# SCH_GPS_lora_mpu_uv_bmp__2022-12-29.net
KiCad netlist of a schematic drawn in EasyEDA
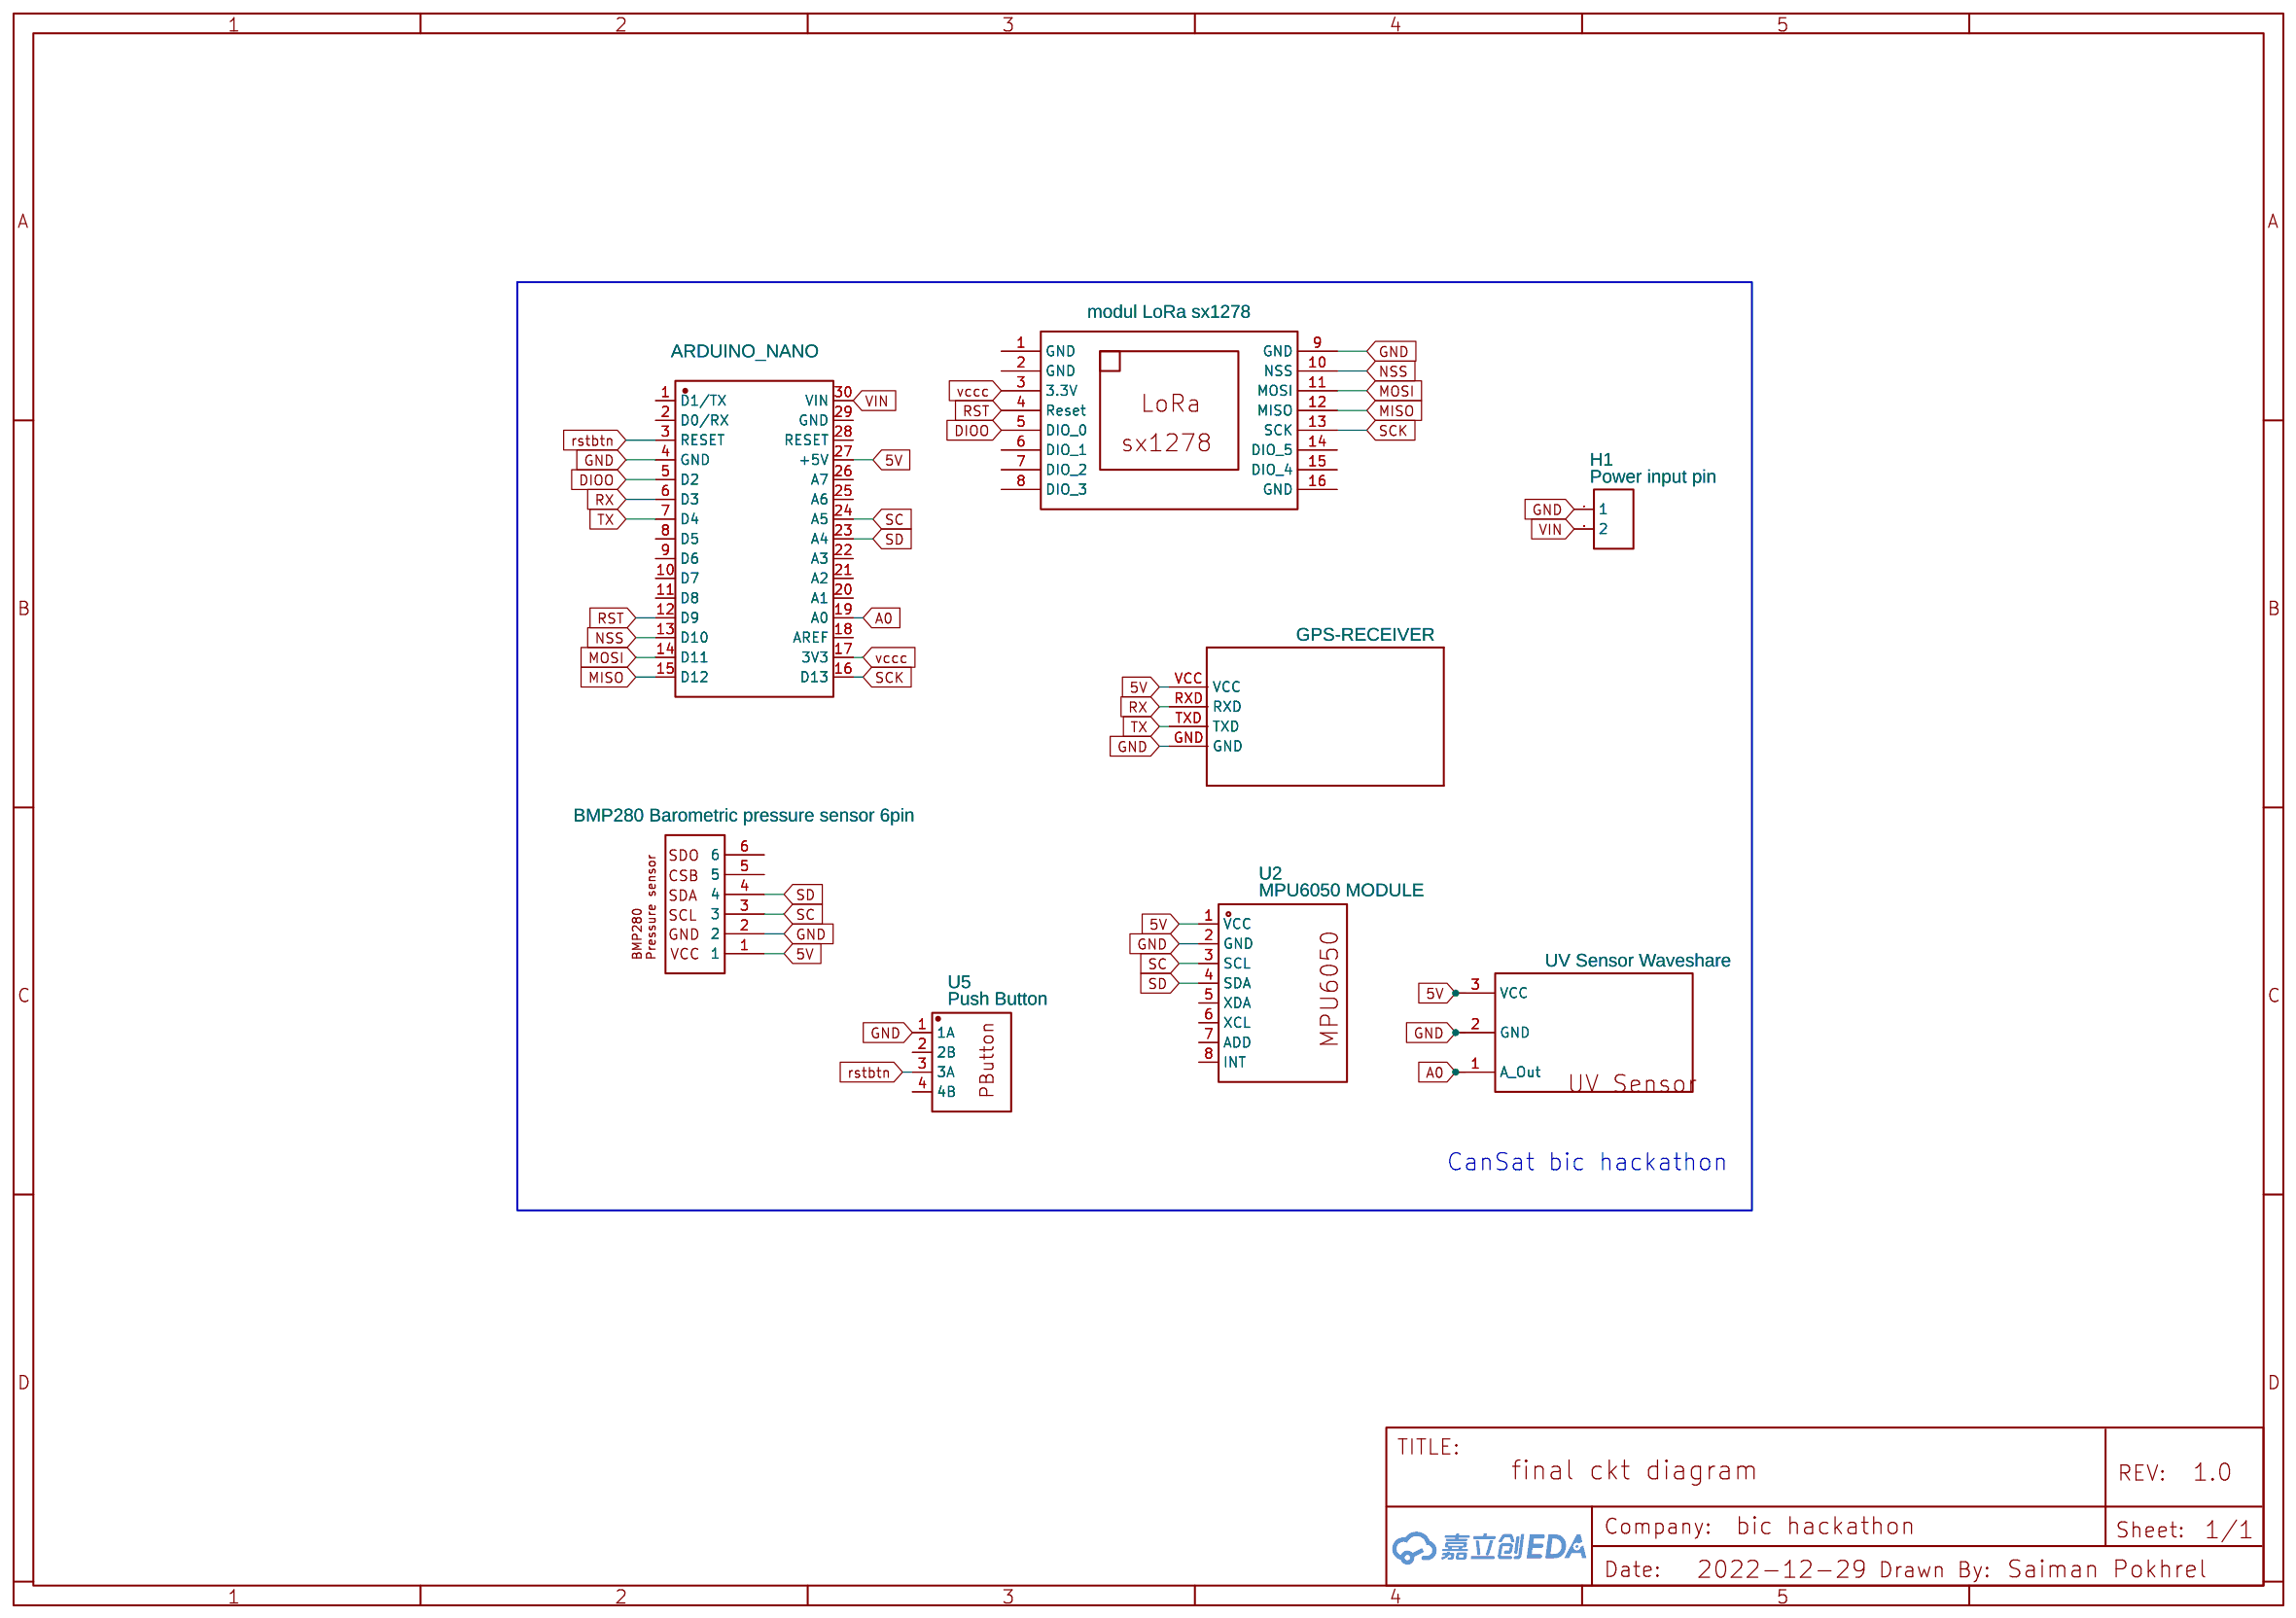
[diagram p0: schematic sheet]

(export (version "E")
  (design (tool "Eeschema 10.0.6"))
  (components
    (comp (ref "1") (value "GPS-RECEIVER") (libsource (lib "") (part "GPS-RECEIVER-NEO8M")))
    (comp (ref "AOUT1")
      (value "UV Sensor Waveshare")
      (fields
        (field (name "BOM_Manufacturer Part") "SKU: 9537")
        (field (name "BOM_Supplier Part") "UV Sensor")
      )
      (libsource (lib "") (part "UV Sensor Waveshare"))
    )
    (comp (ref "H1")
      (value "Power input pin")
      (fields (field (name "BOM_Supplier Part") "C49661"))
      (libsource (lib "") (part "HDR-F-2.54_1x2"))
    )
    (comp (ref "U1")
      (value "BMP280 Barometric pressure sensor 6pin")
      (fields (field (name "BOM_Manufacturer Part") "MAX6675"))
      (libsource (lib "") (part "BMP280 Barometric pressure sensor 6pin"))
    )
    (comp (ref "U2")
      (value "MPU6050 MODULE")
      (fields (field (name "BOM_Manufacturer Part") "MPU6050"))
      (libsource (lib "") (part "MPU6050 MODULE"))
    )
    (comp (ref "U3") (value "modul LoRa sx1278") (libsource (lib "") (part "modul LoRa sx1278")))
    (comp (ref "U4")
      (value "ARDUINO_NANO")
      (fields (field (name "BOM_Supplier Part") "C9900017879"))
      (libsource (lib "") (part "ARDUINO_NANO"))
    )
    (comp (ref "U5") (value "Push Button") (libsource (lib "") (part "Push Button")))
  )
  (nets
    (net (code "1") (name "5V") (class "Default")
      (node (ref "1") (pin "VCC") (pinfunction "VCC_VCC") (pintype "bidirectional"))
      (node (ref "AOUT1") (pin "3") (pinfunction "VCC_3") (pintype "unspecified"))
      (node (ref "U1") (pin "1") (pinfunction "1_1") (pintype "unspecified"))
      (node (ref "U2") (pin "1") (pinfunction "VCC_1") (pintype "passive"))
      (node (ref "U4") (pin "27") (pinfunction "+5V_27") (pintype "unspecified"))
    )
    (net (code "2") (name "A0") (class "Default")
      (node (ref "AOUT1") (pin "1") (pinfunction "A_Out_1") (pintype "unspecified"))
      (node (ref "U4") (pin "19") (pinfunction "A0_19") (pintype "unspecified"))
    )
    (net (code "3") (name "DIOO") (class "Default")
      (node (ref "U3") (pin "5") (pinfunction "DIO_0_5") (pintype "bidirectional"))
      (node (ref "U4") (pin "5") (pinfunction "D2_5") (pintype "unspecified"))
    )
    (net (code "4") (name "GND") (class "Default")
      (node (ref "1") (pin "GND") (pinfunction "GND_GND") (pintype "bidirectional"))
      (node (ref "AOUT1") (pin "2") (pinfunction "GND_2") (pintype "unspecified"))
      (node (ref "H1") (pin "1") (pinfunction "1_1") (pintype "input"))
      (node (ref "U1") (pin "2") (pinfunction "2_2") (pintype "unspecified"))
      (node (ref "U2") (pin "2") (pinfunction "GND_2") (pintype "passive"))
      (node (ref "U3") (pin "9") (pinfunction "GND_9") (pintype "unspecified"))
      (node (ref "U4") (pin "4") (pinfunction "GND_4") (pintype "unspecified"))
      (node (ref "U5") (pin "1") (pinfunction "1A_1") (pintype "unspecified"))
    )
    (net (code "5") (name "MISO") (class "Default")
      (node (ref "U3") (pin "12") (pinfunction "MISO_12") (pintype "output"))
      (node (ref "U4") (pin "15") (pinfunction "D12_15") (pintype "unspecified"))
    )
    (net (code "6") (name "MOSI") (class "Default")
      (node (ref "U3") (pin "11") (pinfunction "MOSI_11") (pintype "input"))
      (node (ref "U4") (pin "14") (pinfunction "D11_14") (pintype "unspecified"))
    )
    (net (code "7") (name "NSS") (class "Default")
      (node (ref "U3") (pin "10") (pinfunction "NSS_10") (pintype "unspecified"))
      (node (ref "U4") (pin "13") (pinfunction "D10_13") (pintype "unspecified"))
    )
    (net (code "8") (name "RST") (class "Default")
      (node (ref "U3") (pin "4") (pinfunction "Reset_4") (pintype "unspecified"))
      (node (ref "U4") (pin "12") (pinfunction "D9_12") (pintype "unspecified"))
    )
    (net (code "9") (name "RX") (class "Default")
      (node (ref "1") (pin "RXD") (pinfunction "RXD_RXD") (pintype "bidirectional"))
      (node (ref "U4") (pin "6") (pinfunction "D3_6") (pintype "unspecified"))
    )
    (net (code "10") (name "SC") (class "Default")
      (node (ref "U1") (pin "3") (pinfunction "3_3") (pintype "unspecified"))
      (node (ref "U2") (pin "3") (pinfunction "SCL_3") (pintype "input"))
      (node (ref "U4") (pin "24") (pinfunction "A5_24") (pintype "unspecified"))
    )
    (net (code "11") (name "SCK") (class "Default")
      (node (ref "U3") (pin "13") (pinfunction "SCK_13") (pintype "unspecified"))
      (node (ref "U4") (pin "16") (pinfunction "D13_16") (pintype "unspecified"))
    )
    (net (code "12") (name "SD") (class "Default")
      (node (ref "U1") (pin "4") (pinfunction "4_4") (pintype "unspecified"))
      (node (ref "U2") (pin "4") (pinfunction "SDA_4") (pintype "bidirectional"))
      (node (ref "U4") (pin "23") (pinfunction "A4_23") (pintype "unspecified"))
    )
    (net (code "13") (name "TX") (class "Default")
      (node (ref "1") (pin "TXD") (pinfunction "TXD_TXD") (pintype "bidirectional"))
      (node (ref "U4") (pin "7") (pinfunction "D4_7") (pintype "unspecified"))
    )
    (net (code "14") (name "VIN") (class "Default")
      (node (ref "H1") (pin "2") (pinfunction "2_2") (pintype "input"))
      (node (ref "U4") (pin "30") (pinfunction "VIN_30") (pintype "unspecified"))
    )
    (net (code "15") (name "rstbtn") (class "Default")
      (node (ref "U4") (pin "3") (pinfunction "RESET_3") (pintype "unspecified"))
      (node (ref "U5") (pin "3") (pinfunction "3A_3") (pintype "unspecified"))
    )
    (net (code "16") (name "unconnected-(U1-Pad5)") (class "Default")
      (node (ref "U1") (pin "5") (pinfunction "5_5") (pintype "unspecified"))
    )
    (net (code "17") (name "unconnected-(U1-Pad6)") (class "Default")
      (node (ref "U1") (pin "6") (pinfunction "6_6") (pintype "unspecified"))
    )
    (net (code "18") (name "unconnected-(U2-ADD-Pad7)") (class "Default")
      (node (ref "U2") (pin "7") (pinfunction "ADD_7") (pintype "unspecified"))
    )
    (net (code "19") (name "unconnected-(U2-INT-Pad8)") (class "Default")
      (node (ref "U2") (pin "8") (pinfunction "INT_8") (pintype "unspecified"))
    )
    (net (code "20") (name "unconnected-(U2-XCL-Pad6)") (class "Default")
      (node (ref "U2") (pin "6") (pinfunction "XCL_6") (pintype "input"))
    )
    (net (code "21") (name "unconnected-(U2-XDA-Pad5)") (class "Default")
      (node (ref "U2") (pin "5") (pinfunction "XDA_5") (pintype "bidirectional"))
    )
    (net (code "22") (name "unconnected-(U3-DIO_1-Pad6)") (class "Default")
      (node (ref "U3") (pin "6") (pinfunction "DIO_1_6") (pintype "bidirectional"))
    )
    (net (code "23") (name "unconnected-(U3-DIO_2-Pad7)") (class "Default")
      (node (ref "U3") (pin "7") (pinfunction "DIO_2_7") (pintype "bidirectional"))
    )
    (net (code "24") (name "unconnected-(U3-DIO_3-Pad8)") (class "Default")
      (node (ref "U3") (pin "8") (pinfunction "DIO_3_8") (pintype "bidirectional"))
    )
    (net (code "25") (name "unconnected-(U3-DIO_4-Pad15)") (class "Default")
      (node (ref "U3") (pin "15") (pinfunction "DIO_4_15") (pintype "bidirectional"))
    )
    (net (code "26") (name "unconnected-(U3-DIO_5-Pad14)") (class "Default")
      (node (ref "U3") (pin "14") (pinfunction "DIO_5_14") (pintype "bidirectional"))
    )
    (net (code "27") (name "unconnected-(U3-GND-Pad1)") (class "Default")
      (node (ref "U3") (pin "1") (pinfunction "GND_1") (pintype "unspecified"))
    )
    (net (code "28") (name "unconnected-(U3-GND-Pad2)") (class "Default")
      (node (ref "U3") (pin "2") (pinfunction "GND_2") (pintype "unspecified"))
    )
    (net (code "29") (name "unconnected-(U3-GND-Pad16)") (class "Default")
      (node (ref "U3") (pin "16") (pinfunction "GND_16") (pintype "unspecified"))
    )
    (net (code "30") (name "unconnected-(U4-A1-Pad20)") (class "Default")
      (node (ref "U4") (pin "20") (pinfunction "A1_20") (pintype "unspecified"))
    )
    (net (code "31") (name "unconnected-(U4-A2-Pad21)") (class "Default")
      (node (ref "U4") (pin "21") (pinfunction "A2_21") (pintype "unspecified"))
    )
    (net (code "32") (name "unconnected-(U4-A3-Pad22)") (class "Default")
      (node (ref "U4") (pin "22") (pinfunction "A3_22") (pintype "unspecified"))
    )
    (net (code "33") (name "unconnected-(U4-A6-Pad25)") (class "Default")
      (node (ref "U4") (pin "25") (pinfunction "A6_25") (pintype "unspecified"))
    )
    (net (code "34") (name "unconnected-(U4-A7-Pad26)") (class "Default")
      (node (ref "U4") (pin "26") (pinfunction "A7_26") (pintype "unspecified"))
    )
    (net (code "35") (name "unconnected-(U4-AREF-Pad18)") (class "Default")
      (node (ref "U4") (pin "18") (pinfunction "AREF_18") (pintype "unspecified"))
    )
    (net (code "36") (name "unconnected-(U4-D0{slash}RX-Pad2)") (class "Default")
      (node (ref "U4") (pin "2") (pinfunction "D0/RX_2") (pintype "unspecified"))
    )
    (net (code "37") (name "unconnected-(U4-D1{slash}TX-Pad1)") (class "Default")
      (node (ref "U4") (pin "1") (pinfunction "D1/TX_1") (pintype "unspecified"))
    )
    (net (code "38") (name "unconnected-(U4-D5-Pad8)") (class "Default")
      (node (ref "U4") (pin "8") (pinfunction "D5_8") (pintype "unspecified"))
    )
    (net (code "39") (name "unconnected-(U4-D6-Pad9)") (class "Default")
      (node (ref "U4") (pin "9") (pinfunction "D6_9") (pintype "unspecified"))
    )
    (net (code "40") (name "unconnected-(U4-D7-Pad10)") (class "Default")
      (node (ref "U4") (pin "10") (pinfunction "D7_10") (pintype "unspecified"))
    )
    (net (code "41") (name "unconnected-(U4-D8-Pad11)") (class "Default")
      (node (ref "U4") (pin "11") (pinfunction "D8_11") (pintype "unspecified"))
    )
    (net (code "42") (name "unconnected-(U4-GND-Pad29)") (class "Default")
      (node (ref "U4") (pin "29") (pinfunction "GND_29") (pintype "unspecified"))
    )
    (net (code "43") (name "unconnected-(U4-RESET-Pad28)") (class "Default")
      (node (ref "U4") (pin "28") (pinfunction "RESET_28") (pintype "unspecified"))
    )
    (net (code "44") (name "unconnected-(U5-2B-Pad2)") (class "Default")
      (node (ref "U5") (pin "2") (pinfunction "2B_2") (pintype "unspecified"))
    )
    (net (code "45") (name "unconnected-(U5-4B-Pad4)") (class "Default")
      (node (ref "U5") (pin "4") (pinfunction "4B_4") (pintype "unspecified"))
    )
    (net (code "46") (name "vccc") (class "Default")
      (node (ref "U3") (pin "3") (pinfunction "3.3V_3") (pintype "passive"))
      (node (ref "U4") (pin "17") (pinfunction "3V3_17") (pintype "unspecified"))
    )
  )
)
